# LT3042_Breakout.net
KiCad netlist of a schematic drawn in EAGLE
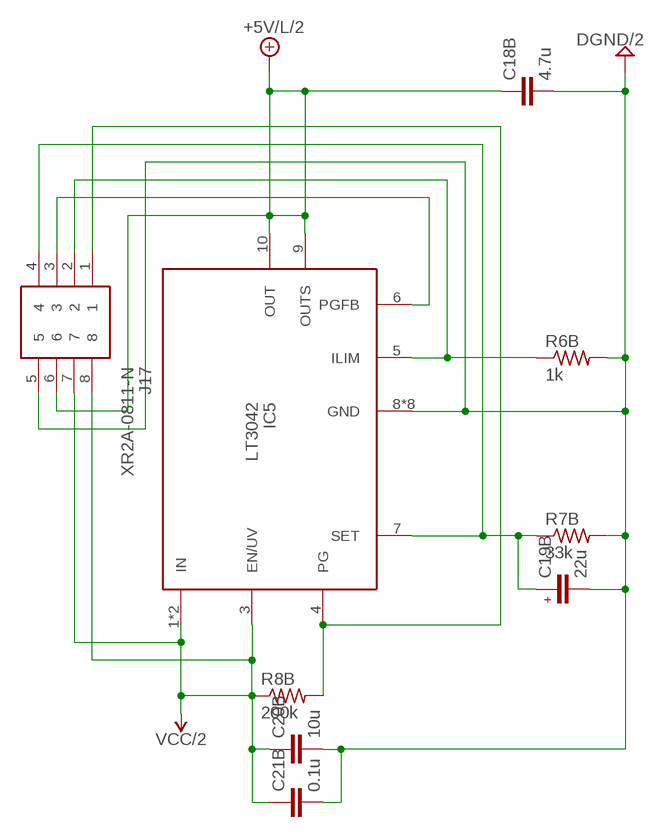
[diagram p0: schematic, sheet 1]

(export (version "E")
  (design (tool "Eeschema 10.0.6"))
  (components
    (comp (ref "C18B")
      (value "4.7u")
      (footprint "eagle-import:CAPC2013X140N")
      (fields
        (field (name "MANUFACTURER_PART_NUMBER") "EMK212ABJ475KG-T")
        (field (name "MOUSER_PART_NUMBER") "963-EMK212ABJ475KG-T")
      )
      (libsource (lib "eagle-import") (part "EMK212ABJ475KG-T"))
    )
    (comp (ref "C19B")
      (value "22u")
      (footprint "eagle-import:C1206")
      (fields
        (field (name "MANUFACTURER_PART_NUMBER") "EMK316BB7226ML-T")
        (field (name "MOUSER_PART_NUMBER") "963-EMK316BB7226ML-T")
      )
      (libsource (lib "eagle-import") (part "EMK316BB7226ML-T"))
    )
    (comp (ref "C20B")
      (value "10u")
      (footprint "eagle-import:CAPC2012X135N")
      (fields
        (field (name "MANUFACTURER_PART_NUMBER") "EMK212BB7106KG-T")
        (field (name "MOUSER_PART_NUMBER") "963-EMK212BB7106KG-T")
      )
      (libsource (lib "eagle-import") (part "EMK212BB7106KG-T"))
    )
    (comp (ref "C21B")
      (value "0.1u")
      (footprint "eagle-import:CAPC2012X135N")
      (fields
        (field (name "MANUFACTURER_PART_NUMBER") "EMF212B7104KGHT")
        (field (name "MOUSER_PART_NUMBER") "963-EMF212B7104KGHT")
      )
      (libsource (lib "eagle-import") (part "EMF212B7104KGHT"))
    )
    (comp (ref "IC5")
      (value "LT3042")
      (footprint "eagle-import:SOP50P490X110-11N")
      (fields
        (field (name "MANUFACTURER_PART_NUMBER") "LT3042EMSE#PBF")
        (field (name "MOUSER_PART_NUMBER") "584-LT3042EMSE#PBF")
      )
      (libsource (lib "eagle-import") (part "LT3042"))
    )
    (comp (ref "J17")
      (value "XR2A-0811-N")
      (footprint "eagle-import:DIPS762W51P254L1016H390Q8N")
      (fields (field (name "MOUSER_PART_NUMBER") "653-XR2A-0811-N"))
      (libsource (lib "eagle-import") (part "XR2A-0811-N"))
    )
    (comp (ref "R6B")
      (value "1k")
      (footprint "eagle-import:RESC2012X60N")
      (fields
        (field (name "MANUFACTURER_PART_NUMBER") "CHP0805-FX-1001ELF")
        (field (name "MOUSER_PART_NUMBER") "652-CHP0805FX1001ELF")
      )
      (libsource (lib "eagle-import") (part "CHP0805-FX-1001ELF"))
    )
    (comp (ref "R7B")
      (value "33k")
      (footprint "eagle-import:R0805")
      (fields
        (field (name "MANUFACTURER_PART_NUMBER") "CPF0805B51KE1")
        (field (name "MOUSER_PART_NUMBER") "279-CPF0805B51KE1")
      )
      (libsource (lib "eagle-import") (part "CPF0805B51KE1"))
    )
    (comp (ref "R8B")
      (value "200k")
      (footprint "eagle-import:R0805")
      (fields
        (field (name "MANUFACTURER_PART_NUMBER") "RR1220P-204-D")
        (field (name "MOUSER_PART_NUMBER") "754-RR1220P-204D")
      )
      (libsource (lib "eagle-import") (part "RR1220P-204-D"))
    )
  )
  (nets
    (net (code "1") (name "+5V{slash}L{slash}2") (class "Default")
      (node (ref "C18B") (pin "1") (pinfunction "1_1") (pintype "passive"))
      (node (ref "IC5") (pin "10") (pinfunction "OUT_10") (pintype "bidirectional"))
      (node (ref "IC5") (pin "9") (pinfunction "OUTS_9") (pintype "bidirectional"))
      (node (ref "J17") (pin "6") (pinfunction "6_6") (pintype "bidirectional"))
    )
    (net (code "2") (name "DGND{slash}2") (class "Default")
      (node (ref "C18B") (pin "2") (pinfunction "2_2") (pintype "passive"))
      (node (ref "C19B") (pin "2") (pinfunction "2_2") (pintype "passive"))
      (node (ref "C19B") (pin "DGND") (pinfunction "2_DGND") (pintype "passive"))
      (node (ref "C20B") (pin "2") (pinfunction "2_2") (pintype "passive"))
      (node (ref "C21B") (pin "2") (pinfunction "2_2") (pintype "passive"))
      (node (ref "IC5") (pin "11") (pinfunction "GND_11") (pintype "bidirectional"))
      (node (ref "IC5") (pin "8") (pinfunction "GND_8") (pintype "bidirectional"))
      (node (ref "IC5") (pin "P$1") (pinfunction "GND_P$1") (pintype "bidirectional"))
      (node (ref "IC5") (pin "P$2") (pinfunction "GND_P$2") (pintype "bidirectional"))
      (node (ref "IC5") (pin "P$3") (pinfunction "GND_P$3") (pintype "bidirectional"))
      (node (ref "IC5") (pin "P$4") (pinfunction "GND_P$4") (pintype "bidirectional"))
      (node (ref "IC5") (pin "P$5") (pinfunction "GND_P$5") (pintype "bidirectional"))
      (node (ref "IC5") (pin "P$6") (pinfunction "GND_P$6") (pintype "bidirectional"))
      (node (ref "J17") (pin "5") (pinfunction "5_5") (pintype "bidirectional"))
      (node (ref "R6B") (pin "2") (pinfunction "2_2") (pintype "passive"))
      (node (ref "R7B") (pin "2") (pinfunction "2_2") (pintype "passive"))
    )
    (net (code "3") (name "Net-(IC5-ILIM)") (class "Default")
      (node (ref "IC5") (pin "5") (pinfunction "ILIM_5") (pintype "bidirectional"))
      (node (ref "J17") (pin "2") (pinfunction "2_2") (pintype "bidirectional"))
      (node (ref "R6B") (pin "1") (pinfunction "1_1") (pintype "passive"))
    )
    (net (code "4") (name "Net-(IC5-PG)") (class "Default")
      (node (ref "IC5") (pin "4") (pinfunction "PG_4") (pintype "bidirectional"))
      (node (ref "J17") (pin "1") (pinfunction "1_1") (pintype "bidirectional"))
      (node (ref "R8B") (pin "2") (pinfunction "2_2") (pintype "passive"))
    )
    (net (code "5") (name "Net-(IC5-PGFB)") (class "Default")
      (node (ref "IC5") (pin "6") (pinfunction "PGFB_6") (pintype "bidirectional"))
      (node (ref "J17") (pin "3") (pinfunction "3_3") (pintype "bidirectional"))
    )
    (net (code "6") (name "Net-(IC5-SET)") (class "Default")
      (node (ref "C19B") (pin "1") (pinfunction "1_1") (pintype "passive"))
      (node (ref "IC5") (pin "7") (pinfunction "SET_7") (pintype "bidirectional"))
      (node (ref "J17") (pin "4") (pinfunction "4_4") (pintype "bidirectional"))
      (node (ref "R7B") (pin "1") (pinfunction "1_1") (pintype "passive"))
    )
    (net (code "7") (name "VCC{slash}2") (class "Default")
      (node (ref "C20B") (pin "1") (pinfunction "1_1") (pintype "passive"))
      (node (ref "C21B") (pin "1") (pinfunction "1_1") (pintype "passive"))
      (node (ref "IC5") (pin "1") (pinfunction "IN_1") (pintype "bidirectional"))
      (node (ref "IC5") (pin "2") (pinfunction "IN_2") (pintype "bidirectional"))
      (node (ref "IC5") (pin "3") (pinfunction "EN/UV_3") (pintype "bidirectional"))
      (node (ref "J17") (pin "7") (pinfunction "7_7") (pintype "bidirectional"))
      (node (ref "J17") (pin "8") (pinfunction "8_8") (pintype "bidirectional"))
      (node (ref "R8B") (pin "1") (pinfunction "1_1") (pintype "passive"))
    )
  )
)
